# Gecko.net
KiCad netlist of a schematic drawn in Altium Designer
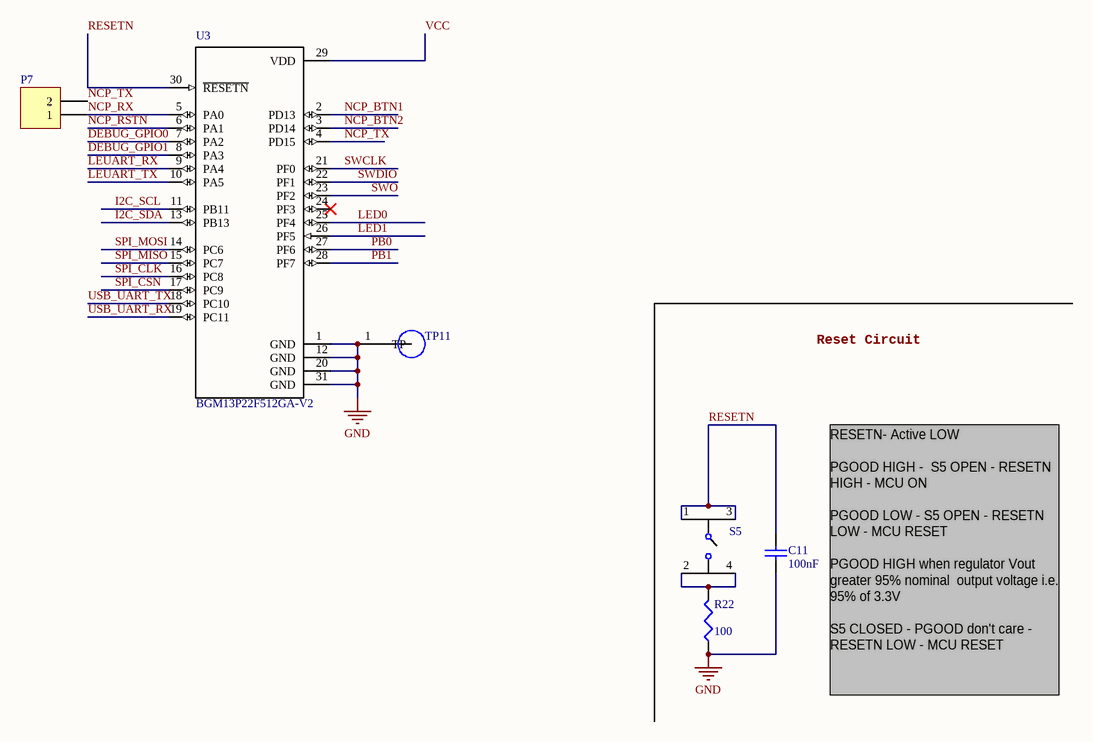
[diagram p0: Gecko.SchDoc]

(export (version "E")
  (design (tool "Eeschema 10.0.6"))
  (components
    (comp (ref "C11")
      (value "100nF")
      (footprint "1608[0603]")
      (description "CAP CER 0.1UF 16V X7R 0603")
      (fields
        (field (name "DIGI-KEY PART NUMBER") "1276-1258-1-ND")
        (field (name "MANUFACTURER") "Samsung Electro-Mechanics")
        (field (name "PUBLISHER") "Altium Limited")
      )
      (libsource (lib "Miscellaneous Devices") (part "Cap"))
    )
    (comp (ref "P7")
      (value "Header 2")
      (footprint "HDR1X2")
      (description "Header, 2-Pin")
      (fields (field (name "PUBLISHER") "Altium Limited"))
      (libsource (lib "Miscellaneous Connectors") (part "Header 2"))
    )
    (comp (ref "R22")
      (value "100")
      (footprint "1608[0603]")
      (description "RES SMD 100 OHM 5% 1/10W 0603")
      (fields
        (field (name "DIGI-KEY PART NUMBER") "541-4059-1-ND")
        (field (name "MANUFACTURER") "Vishay Dale")
        (field (name "PUBLISHER") "Altium Limited")
      )
      (libsource (lib "Miscellaneous Devices") (part "Res3"))
    )
    (comp (ref "S5")
      (value "430182043816")
      (footprint "430182043816")
      (description "SWITCH TACTILE SPST-NO 0.05A 12V")
      (fields
        (field (name "MANUFACTURER") "Wurth Electronics")
        (field (name "DIGI-KEY PART NUMBER") "732-7004-1-ND")
      )
      (libsource (lib "430182043816") (part "430182043816"))
    )
    (comp (ref "TP11")
      (value "5019")
      (footprint "TP380X203")
      (description "PC TEST POINT MINIATURE")
      (fields (field (name "DIGI-KEY_PART_NUMBER") "36-5019CT-ND") (field (name "MF") "Keystone"))
      (libsource (lib "5019") (part "5019"))
    )
    (comp (ref "U3")
      (value "BGM13P22F512GA-V2")
      (footprint "MODULE_BGM13P22F512GA-V2")
      (description "EFR32BG13 Bluetooth 5.0 Module, 512kB Flash, +8dbm")
      (fields
        (field (name "MANUFACTURER") "Silicon Labs")
        (field (name "DIGI-KEY PART NUMBER") "336-5465-1-ND")
      )
      (libsource (lib "BGM13P22F512GA-V2") (part "BGM13P22F512GA-V2"))
    )
  )
  (nets
    (net (code "1") (name "/DEBUG_GPIO0") (class "Default")
      (node (ref "U3") (pin "7") (pinfunction "PA2_7") (pintype "bidirectional"))
    )
    (net (code "2") (name "/DEBUG_GPIO1") (class "Default")
      (node (ref "U3") (pin "8") (pinfunction "PA3_8") (pintype "bidirectional"))
    )
    (net (code "3") (name "/I2C_SCL") (class "Default")
      (node (ref "U3") (pin "11") (pinfunction "PB11_11") (pintype "bidirectional"))
    )
    (net (code "4") (name "/I2C_SDA") (class "Default")
      (node (ref "U3") (pin "13") (pinfunction "PB13_13") (pintype "bidirectional"))
    )
    (net (code "5") (name "/LED0") (class "Default")
      (node (ref "U3") (pin "25") (pinfunction "PF4_25") (pintype "bidirectional"))
    )
    (net (code "6") (name "/LED1") (class "Default")
      (node (ref "U3") (pin "26") (pinfunction "PF5_26") (pintype "input"))
    )
    (net (code "7") (name "/LEUART_RX") (class "Default")
      (node (ref "U3") (pin "9") (pinfunction "PA4_9") (pintype "bidirectional"))
    )
    (net (code "8") (name "/LEUART_TX") (class "Default")
      (node (ref "U3") (pin "10") (pinfunction "PA5_10") (pintype "bidirectional"))
    )
    (net (code "9") (name "/NCP_BTN1") (class "Default")
      (node (ref "U3") (pin "2") (pinfunction "PD13_2") (pintype "bidirectional"))
    )
    (net (code "10") (name "/NCP_BTN2") (class "Default")
      (node (ref "U3") (pin "3") (pinfunction "PD14_3") (pintype "bidirectional"))
    )
    (net (code "11") (name "/NCP_RSTN") (class "Default")
      (node (ref "U3") (pin "6") (pinfunction "PA1_6") (pintype "bidirectional"))
    )
    (net (code "12") (name "/NCP_RX") (class "Default")
      (node (ref "P7") (pin "1") (pinfunction "1_1") (pintype "passive"))
      (node (ref "U3") (pin "5") (pinfunction "PA0_5") (pintype "bidirectional"))
    )
    (net (code "13") (name "/NCP_TX") (class "Default")
      (node (ref "P7") (pin "2") (pinfunction "2_2") (pintype "passive"))
      (node (ref "U3") (pin "4") (pinfunction "PD15_4") (pintype "bidirectional"))
    )
    (net (code "14") (name "/PB0") (class "Default")
      (node (ref "U3") (pin "27") (pinfunction "PF6_27") (pintype "bidirectional"))
    )
    (net (code "15") (name "/PB1") (class "Default")
      (node (ref "U3") (pin "28") (pinfunction "PF7_28") (pintype "bidirectional"))
    )
    (net (code "16") (name "/RESETN") (class "Default")
      (node (ref "C11") (pin "1") (pinfunction "1_1") (pintype "passive"))
      (node (ref "S5") (pin "1") (pinfunction "1_1") (pintype "passive"))
      (node (ref "S5") (pin "3") (pinfunction "3_3") (pintype "passive"))
      (node (ref "U3") (pin "30") (pinfunction "~{RESETN}_30") (pintype "input"))
    )
    (net (code "17") (name "/SPI_CLK") (class "Default")
      (node (ref "U3") (pin "16") (pinfunction "PC8_16") (pintype "bidirectional"))
    )
    (net (code "18") (name "/SPI_CSN") (class "Default")
      (node (ref "U3") (pin "17") (pinfunction "PC9_17") (pintype "bidirectional"))
    )
    (net (code "19") (name "/SPI_MISO") (class "Default")
      (node (ref "U3") (pin "15") (pinfunction "PC7_15") (pintype "bidirectional"))
    )
    (net (code "20") (name "/SPI_MOSI") (class "Default")
      (node (ref "U3") (pin "14") (pinfunction "PC6_14") (pintype "bidirectional"))
    )
    (net (code "21") (name "/SWCLK") (class "Default")
      (node (ref "U3") (pin "21") (pinfunction "PF0_21") (pintype "bidirectional"))
    )
    (net (code "22") (name "/SWDIO") (class "Default")
      (node (ref "U3") (pin "22") (pinfunction "PF1_22") (pintype "bidirectional"))
    )
    (net (code "23") (name "/SWO") (class "Default")
      (node (ref "U3") (pin "23") (pinfunction "PF2_23") (pintype "bidirectional"))
    )
    (net (code "24") (name "/USB_UART_RX") (class "Default")
      (node (ref "U3") (pin "19") (pinfunction "PC11_19") (pintype "bidirectional"))
    )
    (net (code "25") (name "/USB_UART_TX") (class "Default")
      (node (ref "U3") (pin "18") (pinfunction "PC10_18") (pintype "bidirectional"))
    )
    (net (code "26") (name "/VCC") (class "Default")
      (node (ref "U3") (pin "29") (pinfunction "VDD_29") (pintype "power_in"))
    )
    (net (code "27") (name "GND") (class "Default")
      (node (ref "C11") (pin "2") (pinfunction "2_2") (pintype "passive"))
      (node (ref "R22") (pin "1") (pinfunction "1_1") (pintype "passive"))
      (node (ref "TP11") (pin "1") (pinfunction "TP_1") (pintype "passive"))
      (node (ref "U3") (pin "1") (pinfunction "GND_1") (pintype "power_in"))
      (node (ref "U3") (pin "12") (pinfunction "GND_12") (pintype "power_in"))
      (node (ref "U3") (pin "20") (pinfunction "GND_20") (pintype "power_in"))
      (node (ref "U3") (pin "31") (pinfunction "GND_31") (pintype "power_in"))
    )
    (net (code "28") (name "Net-(R22-Pad2)") (class "Default")
      (node (ref "R22") (pin "2") (pinfunction "2_2") (pintype "passive"))
      (node (ref "S5") (pin "2") (pinfunction "2_2") (pintype "passive"))
      (node (ref "S5") (pin "4") (pinfunction "4_4") (pintype "passive"))
    )
    (net (code "29") (name "unconnected-(U3-PF3-Pad24)") (class "Default")
      (node (ref "U3") (pin "24") (pinfunction "PF3_24") (pintype "bidirectional+no_connect"))
    )
  )
)
